# Transceiver_Module_Dev_Board_without_MCU.net
KiCad netlist of a schematic drawn in EAGLE
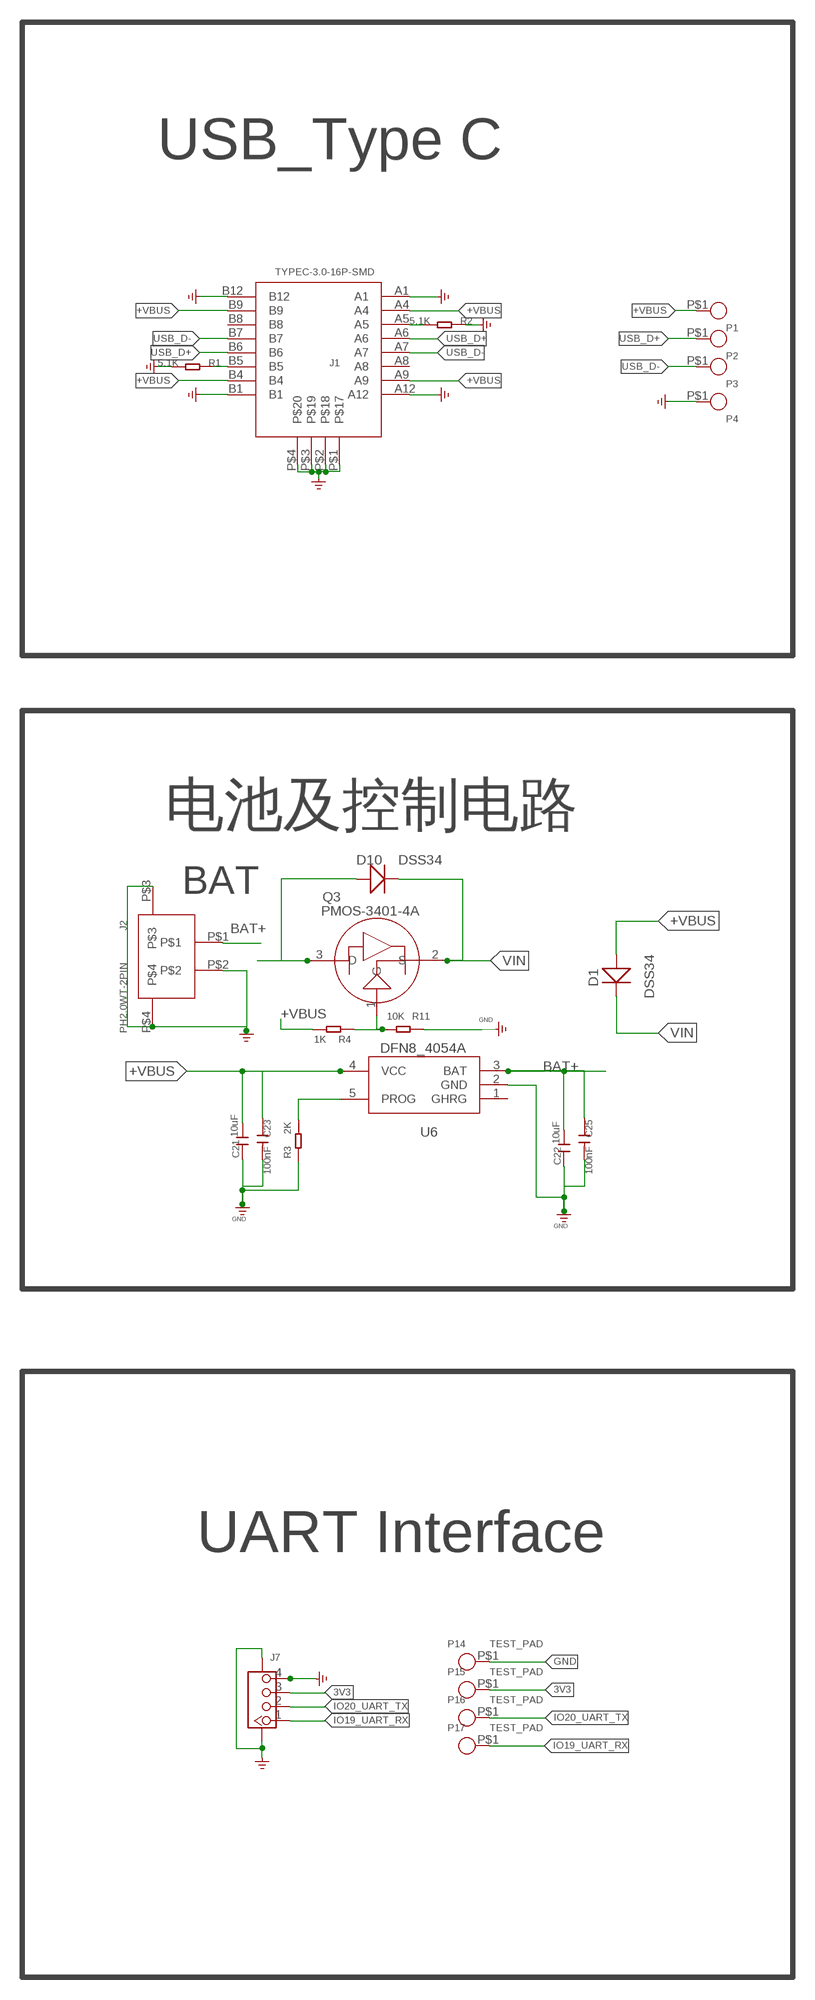
[diagram p0: schematic, sheet 1, part 1 of 2]
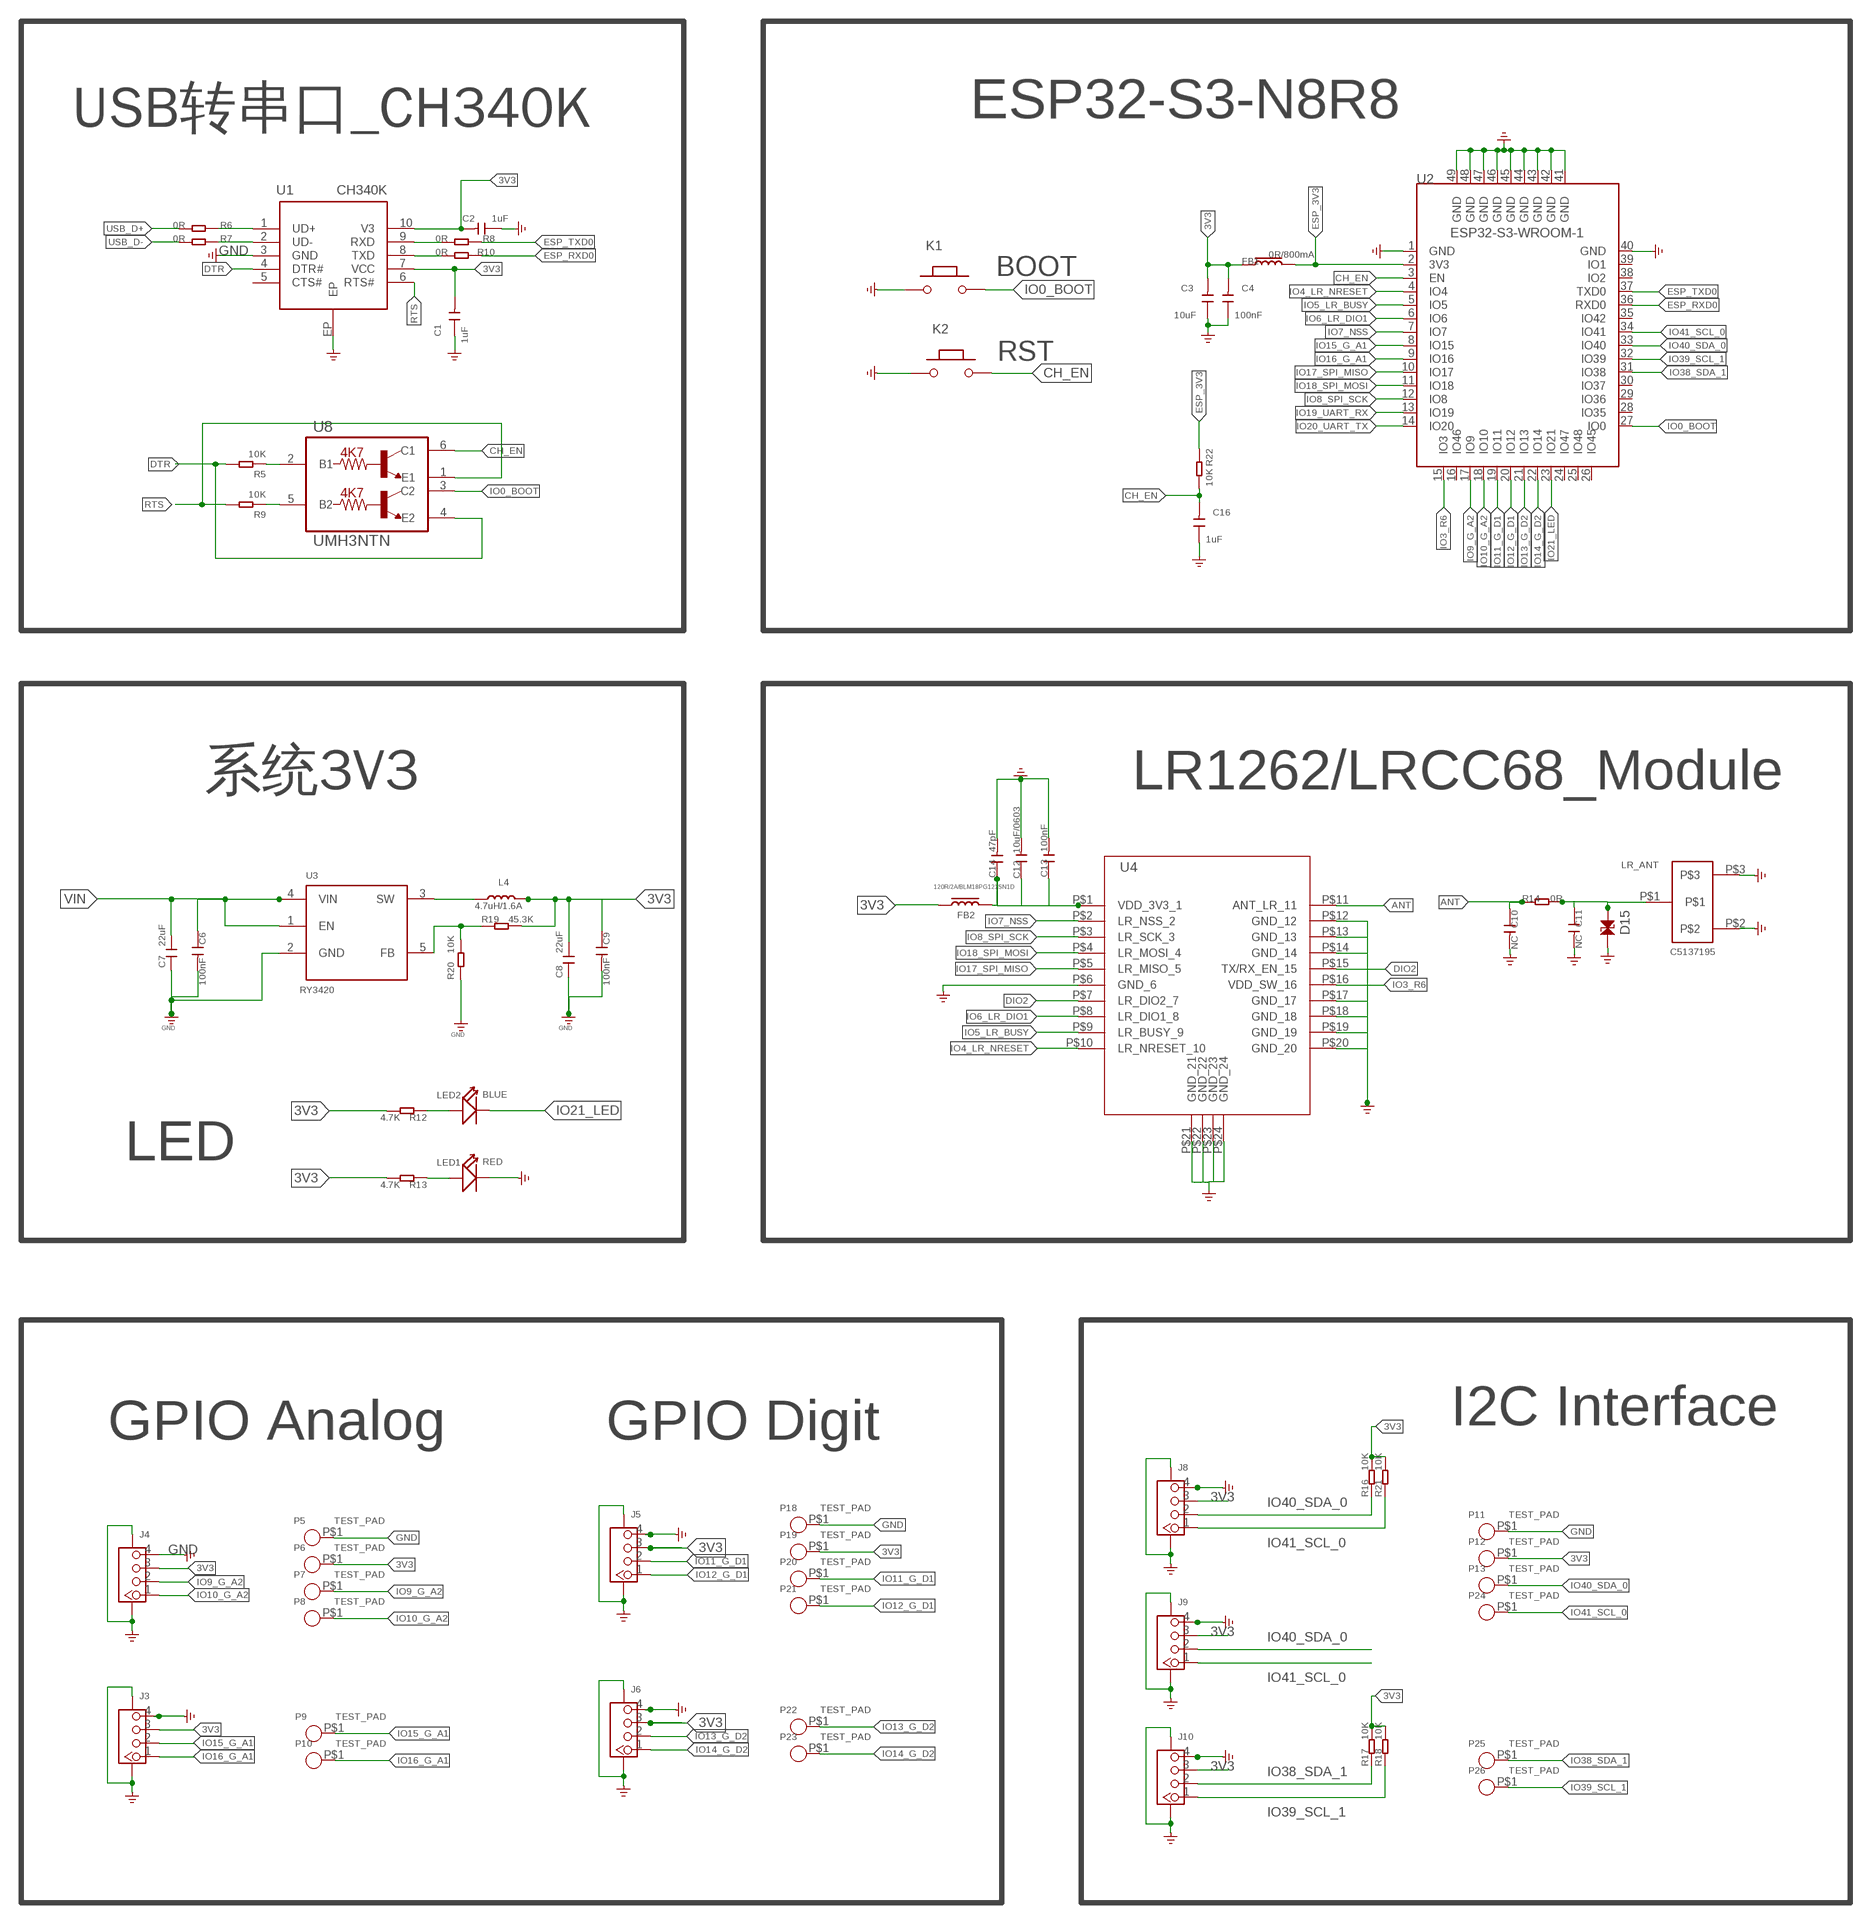
[diagram p1: schematic, sheet 1, part 2 of 2]

(export (version "E")
  (design (tool "Eeschema 10.0.6"))
  (components
    (comp (ref "C1")
      (value "1uF")
      (footprint "eagle-import:C0603")
      (libsource (lib "eagle-import") (part "CAP"))
    )
    (comp (ref "C2")
      (value "1uF")
      (footprint "eagle-import:C0603")
      (libsource (lib "eagle-import") (part "CAP"))
    )
    (comp (ref "C3")
      (value "10uF")
      (footprint "eagle-import:C0603")
      (libsource (lib "eagle-import") (part "CAP"))
    )
    (comp (ref "C4")
      (value "100nF")
      (footprint "eagle-import:C0603")
      (libsource (lib "eagle-import") (part "CAP"))
    )
    (comp (ref "C6")
      (value "100nF")
      (footprint "eagle-import:C0402")
      (libsource (lib "eagle-import") (part "SX1302_Module_CAPC0402-1"))
    )
    (comp (ref "C7")
      (value "22uF")
      (footprint "eagle-import:0603")
      (libsource (lib "eagle-import") (part "WGH_C0603"))
    )
    (comp (ref "C8")
      (value "22uF")
      (footprint "eagle-import:0603")
      (libsource (lib "eagle-import") (part "WGH_C0603"))
    )
    (comp (ref "C9")
      (value "100nF")
      (footprint "eagle-import:C0402")
      (libsource (lib "eagle-import") (part "SX1302_Module_CAPC0402-1"))
    )
    (comp (ref "C10")
      (value "NC")
      (footprint "eagle-import:C0402")
      (libsource (lib "eagle-import") (part "SX1302_Module_CAPC0402-1"))
    )
    (comp (ref "C11")
      (value "NC")
      (footprint "eagle-import:C0402")
      (libsource (lib "eagle-import") (part "SX1302_Module_CAPC0402-1"))
    )
    (comp (ref "C12")
      (value "10uF/0603")
      (footprint "eagle-import:C0603")
      (libsource (lib "eagle-import") (part "C0603"))
    )
    (comp (ref "C13")
      (value "100nF")
      (footprint "eagle-import:C0402")
      (libsource (lib "eagle-import") (part "SX1302_Module_CAPC0402-1"))
    )
    (comp (ref "C14")
      (value "47pF")
      (footprint "eagle-import:C0402")
      (libsource (lib "eagle-import") (part "SX1302_Module_CAPC0402-1"))
    )
    (comp (ref "C16")
      (value "1uF")
      (footprint "eagle-import:C0603")
      (libsource (lib "eagle-import") (part "CAP"))
    )
    (comp (ref "C21")
      (value "10uF")
      (footprint "eagle-import:0402")
      (libsource (lib "eagle-import") (part "C0402_W"))
    )
    (comp (ref "C22")
      (value "10uF")
      (footprint "eagle-import:0402")
      (libsource (lib "eagle-import") (part "C0402_W"))
    )
    (comp (ref "C23")
      (value "100nF")
      (footprint "eagle-import:C0402")
      (libsource (lib "eagle-import") (part "SX1302_Module_CAPC0402-1"))
    )
    (comp (ref "C25")
      (value "100nF")
      (footprint "eagle-import:C0402")
      (libsource (lib "eagle-import") (part "SX1302_Module_CAPC0402-1"))
    )
    (comp (ref "D1")
      (value "DSS34")
      (footprint "eagle-import:D_SOD123FL")
      (libsource (lib "eagle-import") (part "DIODE"))
    )
    (comp (ref "D10")
      (value "DSS34")
      (footprint "eagle-import:D_SOD123FL")
      (libsource (lib "eagle-import") (part "DIODE"))
    )
    (comp (ref "D15")
      (value "LXES15AAA1-153")
      (footprint "eagle-import:0402-ESD")
      (libsource (lib "eagle-import") (part "LXES15AAA1-153"))
    )
    (comp (ref "FB1")
      (value "0R/800mA")
      (footprint "eagle-import:L0603")
      (libsource (lib "eagle-import") (part "FBL0603"))
    )
    (comp (ref "FB2")
      (value "120R/2A/BLM18PG121SN1D")
      (footprint "eagle-import:L0603")
      (libsource (lib "eagle-import") (part "LoraWAN_Gateway_Mainboard_FBL0603"))
    )
    (comp (ref "J1")
      (value "TYPEC-3.0-16P-SMD")
      (footprint "eagle-import:USB-3.0TYPEC-SMD")
      (libsource (lib "eagle-import") (part "TYPEC-3.0-16P-SMD"))
    )
    (comp (ref "J2")
      (value "PH2.0WT-2PIN")
      (footprint "eagle-import:PH2.0WT-2PIN")
      (libsource (lib "eagle-import") (part "PH2.0WT-2PIN"))
    )
    (comp (ref "J3")
      (value "CONNECTOR_TWIG-4P-2.0-SMD-FEMALE-REINFORCE90D")
      (footprint "eagle-import:CONNECTOR_4P-SMD-2.0-90D")
      (libsource (lib "eagle-import") (part "CONNECTOR_TWIG-4P-2.0-SMD-FEMALE-REINFORCE90D"))
    )
    (comp (ref "J4")
      (value "CONNECTOR_TWIG-4P-2.0-SMD-FEMALE-REINFORCE90D")
      (footprint "eagle-import:CONNECTOR_4P-SMD-2.0-90D")
      (libsource (lib "eagle-import") (part "CONNECTOR_TWIG-4P-2.0-SMD-FEMALE-REINFORCE90D"))
    )
    (comp (ref "J5")
      (value "CONNECTOR_TWIG-4P-2.0-SMD-FEMALE-REINFORCE90D")
      (footprint "eagle-import:CONNECTOR_4P-SMD-2.0-90D")
      (libsource (lib "eagle-import") (part "CONNECTOR_TWIG-4P-2.0-SMD-FEMALE-REINFORCE90D"))
    )
    (comp (ref "J6")
      (value "CONNECTOR_TWIG-4P-2.0-SMD-FEMALE-REINFORCE90D")
      (footprint "eagle-import:CONNECTOR_4P-SMD-2.0-90D")
      (libsource (lib "eagle-import") (part "CONNECTOR_TWIG-4P-2.0-SMD-FEMALE-REINFORCE90D"))
    )
    (comp (ref "J7")
      (value "CONNECTOR_TWIG-4P-2.0-SMD-FEMALE-REINFORCE90D")
      (footprint "eagle-import:CONNECTOR_4P-SMD-2.0-90D")
      (libsource (lib "eagle-import") (part "CONNECTOR_TWIG-4P-2.0-SMD-FEMALE-REINFORCE90D"))
    )
    (comp (ref "J8")
      (value "CONNECTOR_TWIG-4P-2.0-SMD-FEMALE-REINFORCE90D")
      (footprint "eagle-import:CONNECTOR_4P-SMD-2.0-90D")
      (libsource (lib "eagle-import") (part "CONNECTOR_TWIG-4P-2.0-SMD-FEMALE-REINFORCE90D"))
    )
    (comp (ref "J9")
      (value "CONNECTOR_TWIG-4P-2.0-SMD-FEMALE-REINFORCE90D")
      (footprint "eagle-import:CONNECTOR_4P-SMD-2.0-90D")
      (libsource (lib "eagle-import") (part "CONNECTOR_TWIG-4P-2.0-SMD-FEMALE-REINFORCE90D"))
    )
    (comp (ref "J10")
      (value "CONNECTOR_TWIG-4P-2.0-SMD-FEMALE-REINFORCE90D")
      (footprint "eagle-import:CONNECTOR_4P-SMD-2.0-90D")
      (libsource (lib "eagle-import") (part "CONNECTOR_TWIG-4P-2.0-SMD-FEMALE-REINFORCE90D"))
    )
    (comp (ref "K1")
      (value "BUTTON")
      (footprint "eagle-import:157SW")
      (libsource (lib "eagle-import") (part "PB157"))
    )
    (comp (ref "K2")
      (value "BUTTON")
      (footprint "eagle-import:157SW")
      (libsource (lib "eagle-import") (part "PB157"))
    )
    (comp (ref "L4")
      (value "4.7uH/1.6A")
      (footprint "eagle-import:A9G_DISCRETE_L0805")
      (libsource (lib "eagle-import") (part "A9G_DISCRETE_L0805"))
    )
    (comp (ref "LED1")
      (value "RED")
      (footprint "eagle-import:DISCRETE_LED-0603")
      (libsource (lib "eagle-import") (part "DISCRETE_LED0603"))
    )
    (comp (ref "LED2")
      (value "BLUE")
      (footprint "eagle-import:DISCRETE_LED-0603")
      (libsource (lib "eagle-import") (part "DISCRETE_LED0603"))
    )
    (comp (ref "LR_ANT")
      (value "C5137195")
      (footprint "eagle-import:MYSELF_IPEX1")
      (libsource (lib "eagle-import") (part "MYSELF_IPEX"))
    )
    (comp (ref "P1")
      (value "TEST_PADPAD-1.5MM")
      (footprint "eagle-import:TEST_PAD-1.5MM")
      (libsource (lib "eagle-import") (part "CrowPanel_Advance_HMI_TEST_PADPAD-1.5MM"))
    )
    (comp (ref "P2")
      (value "TEST_PADPAD-1.5MM")
      (footprint "eagle-import:TEST_PAD-1.5MM")
      (libsource (lib "eagle-import") (part "CrowPanel_Advance_HMI_TEST_PADPAD-1.5MM"))
    )
    (comp (ref "P3")
      (value "TEST_PADPAD-1.5MM")
      (footprint "eagle-import:TEST_PAD-1.5MM")
      (libsource (lib "eagle-import") (part "CrowPanel_Advance_HMI_TEST_PADPAD-1.5MM"))
    )
    (comp (ref "P4")
      (value "TEST_PADPAD-1.5MM")
      (footprint "eagle-import:TEST_PAD-1.5MM")
      (libsource (lib "eagle-import") (part "CrowPanel_Advance_HMI_TEST_PADPAD-1.5MM"))
    )
    (comp (ref "P5")
      (value "TEST_PAD")
      (footprint "eagle-import:TEST_PAD-1.5MM")
      (libsource (lib "eagle-import") (part "TEST_PADPAD-1.5MM"))
    )
    (comp (ref "P6")
      (value "TEST_PAD")
      (footprint "eagle-import:TEST_PAD-1.5MM")
      (libsource (lib "eagle-import") (part "TEST_PADPAD-1.5MM"))
    )
    (comp (ref "P7")
      (value "TEST_PAD")
      (footprint "eagle-import:TEST_PAD-1.5MM")
      (libsource (lib "eagle-import") (part "TEST_PADPAD-1.5MM"))
    )
    (comp (ref "P8")
      (value "TEST_PAD")
      (footprint "eagle-import:TEST_PAD-1.5MM")
      (libsource (lib "eagle-import") (part "TEST_PADPAD-1.5MM"))
    )
    (comp (ref "P9")
      (value "TEST_PAD")
      (footprint "eagle-import:TEST_PAD-1.5MM")
      (libsource (lib "eagle-import") (part "TEST_PADPAD-1.5MM"))
    )
    (comp (ref "P10")
      (value "TEST_PAD")
      (footprint "eagle-import:TEST_PAD-1.5MM")
      (libsource (lib "eagle-import") (part "TEST_PADPAD-1.5MM"))
    )
    (comp (ref "P11")
      (value "TEST_PAD")
      (footprint "eagle-import:TEST_PAD-1.5MM")
      (libsource (lib "eagle-import") (part "TEST_PADPAD-1.5MM"))
    )
    (comp (ref "P12")
      (value "TEST_PAD")
      (footprint "eagle-import:TEST_PAD-1.5MM")
      (libsource (lib "eagle-import") (part "TEST_PADPAD-1.5MM"))
    )
    (comp (ref "P13")
      (value "TEST_PAD")
      (footprint "eagle-import:TEST_PAD-1.5MM")
      (libsource (lib "eagle-import") (part "TEST_PADPAD-1.5MM"))
    )
    (comp (ref "P14")
      (value "TEST_PAD")
      (footprint "eagle-import:TEST_PAD-1.5MM")
      (libsource (lib "eagle-import") (part "TEST_PADPAD-1.5MM"))
    )
    (comp (ref "P15")
      (value "TEST_PAD")
      (footprint "eagle-import:TEST_PAD-1.5MM")
      (libsource (lib "eagle-import") (part "TEST_PADPAD-1.5MM"))
    )
    (comp (ref "P16")
      (value "TEST_PAD")
      (footprint "eagle-import:TEST_PAD-1.5MM")
      (libsource (lib "eagle-import") (part "TEST_PADPAD-1.5MM"))
    )
    (comp (ref "P17")
      (value "TEST_PAD")
      (footprint "eagle-import:TEST_PAD-1.5MM")
      (libsource (lib "eagle-import") (part "TEST_PADPAD-1.5MM"))
    )
    (comp (ref "P18")
      (value "TEST_PAD")
      (footprint "eagle-import:TEST_PAD-1.5MM")
      (libsource (lib "eagle-import") (part "TEST_PADPAD-1.5MM"))
    )
    (comp (ref "P19")
      (value "TEST_PAD")
      (footprint "eagle-import:TEST_PAD-1.5MM")
      (libsource (lib "eagle-import") (part "TEST_PADPAD-1.5MM"))
    )
    (comp (ref "P20")
      (value "TEST_PAD")
      (footprint "eagle-import:TEST_PAD-1.5MM")
      (libsource (lib "eagle-import") (part "TEST_PADPAD-1.5MM"))
    )
    (comp (ref "P21")
      (value "TEST_PAD")
      (footprint "eagle-import:TEST_PAD-1.5MM")
      (libsource (lib "eagle-import") (part "TEST_PADPAD-1.5MM"))
    )
    (comp (ref "P22")
      (value "TEST_PAD")
      (footprint "eagle-import:TEST_PAD-1.5MM")
      (libsource (lib "eagle-import") (part "TEST_PADPAD-1.5MM"))
    )
    (comp (ref "P23")
      (value "TEST_PAD")
      (footprint "eagle-import:TEST_PAD-1.5MM")
      (libsource (lib "eagle-import") (part "TEST_PADPAD-1.5MM"))
    )
    (comp (ref "P24")
      (value "TEST_PAD")
      (footprint "eagle-import:TEST_PAD-1.5MM")
      (libsource (lib "eagle-import") (part "TEST_PADPAD-1.5MM"))
    )
    (comp (ref "P25")
      (value "TEST_PAD")
      (footprint "eagle-import:TEST_PAD-1.5MM")
      (libsource (lib "eagle-import") (part "TEST_PADPAD-1.5MM"))
    )
    (comp (ref "P26")
      (value "TEST_PAD")
      (footprint "eagle-import:TEST_PAD-1.5MM")
      (libsource (lib "eagle-import") (part "TEST_PADPAD-1.5MM"))
    )
    (comp (ref "Q3")
      (value "PMOS-3401-4A")
      (footprint "eagle-import:SOT-23")
      (libsource (lib "eagle-import") (part "P-MOS-SOT23"))
    )
    (comp (ref "R1")
      (value "5.1K")
      (footprint "eagle-import:R0603-SP")
      (libsource (lib "eagle-import") (part "RES-0603"))
    )
    (comp (ref "R2")
      (value "5.1K")
      (footprint "eagle-import:R0603-SP")
      (libsource (lib "eagle-import") (part "RES-0603"))
    )
    (comp (ref "R3")
      (value "2K")
      (footprint "eagle-import:0402")
      (libsource (lib "eagle-import") (part "R0402-1"))
    )
    (comp (ref "R4")
      (value "1K")
      (footprint "eagle-import:0402")
      (libsource (lib "eagle-import") (part "R0402-1"))
    )
    (comp (ref "R5")
      (value "10K")
      (footprint "eagle-import:R0603-SP")
      (libsource (lib "eagle-import") (part "RES-0603"))
    )
    (comp (ref "R6")
      (value "0R")
      (footprint "eagle-import:R0603-SP")
      (libsource (lib "eagle-import") (part "RES-0603"))
    )
    (comp (ref "R7")
      (value "0R")
      (footprint "eagle-import:R0603-SP")
      (libsource (lib "eagle-import") (part "RES-0603"))
    )
    (comp (ref "R8")
      (value "0R")
      (footprint "eagle-import:R0603-SP")
      (libsource (lib "eagle-import") (part "RES-0603"))
    )
    (comp (ref "R9")
      (value "10K")
      (footprint "eagle-import:R0603-SP")
      (libsource (lib "eagle-import") (part "RES-0603"))
    )
    (comp (ref "R10")
      (value "0R")
      (footprint "eagle-import:R0603-SP")
      (libsource (lib "eagle-import") (part "RES-0603"))
    )
    (comp (ref "R11")
      (value "10K")
      (footprint "eagle-import:0402")
      (libsource (lib "eagle-import") (part "R0402-1"))
    )
    (comp (ref "R12")
      (value "4.7K")
      (footprint "eagle-import:0402")
      (libsource (lib "eagle-import") (part "R0402-1"))
    )
    (comp (ref "R13")
      (value "4.7K")
      (footprint "eagle-import:0402")
      (libsource (lib "eagle-import") (part "R0402-1"))
    )
    (comp (ref "R14")
      (value "0R")
      (footprint "eagle-import:R0402")
      (libsource (lib "eagle-import") (part "LoraWAN_Gateway_Mainboard_RES-0402"))
    )
    (comp (ref "R16")
      (value "10K")
      (footprint "eagle-import:0402")
      (libsource (lib "eagle-import") (part "R0402-1"))
    )
    (comp (ref "R17")
      (value "10K")
      (footprint "eagle-import:0402")
      (libsource (lib "eagle-import") (part "R0402-1"))
    )
    (comp (ref "R18")
      (value "10K")
      (footprint "eagle-import:0402")
      (libsource (lib "eagle-import") (part "R0402-1"))
    )
    (comp (ref "R19")
      (value "45.3K")
      (footprint "eagle-import:0402")
      (libsource (lib "eagle-import") (part "R0402-1"))
    )
    (comp (ref "R20")
      (value "10K")
      (footprint "eagle-import:0402")
      (libsource (lib "eagle-import") (part "R0402-1"))
    )
    (comp (ref "R21")
      (value "10K")
      (footprint "eagle-import:0402")
      (libsource (lib "eagle-import") (part "R0402-1"))
    )
    (comp (ref "R22")
      (value "10K")
      (footprint "eagle-import:R0603-SP")
      (libsource (lib "eagle-import") (part "RES-0603"))
    )
    (comp (ref "U1")
      (value "CH340K")
      (footprint "eagle-import:ESOP-10-EP-150MIL")
      (libsource (lib "eagle-import") (part "CH340K"))
    )
    (comp (ref "U2")
      (value "ESP32-S3-WROOM-1")
      (footprint "eagle-import:ESP32-S3-WROOM-1-SMD41")
      (libsource (lib "eagle-import") (part "ESP32-S3-WROOM-1"))
    )
    (comp (ref "U3")
      (value "RY3420")
      (footprint "eagle-import:CROWBOT_-V1.0-20220525_A_XBJ_SOT23-5")
      (libsource (lib "eagle-import") (part "CROWBOT_-V1.0-20220525_A_XBJ_HM3420B"))
    )
    (comp (ref "U4")
      (value "LR1262_LRCC68_MD_1010MM")
      (footprint "eagle-import:LR1262_LRCC68_MD_10_10MM")
      (libsource (lib "eagle-import") (part "LR1262_LRCC68_MD_1010MM"))
    )
    (comp (ref "U6")
      (value "DFN8_4054A")
      (footprint "eagle-import:DFN8_SOP23-5")
      (libsource (lib "eagle-import") (part "DFN8_4054A"))
    )
    (comp (ref "U8")
      (value "UMH3NTN")
      (footprint "eagle-import:SOP65P210X100-6N")
      (fields (field (name "MF") "Rohm"))
      (libsource (lib "eagle-import") (part "UMH3NTN"))
    )
  )
  (nets
    (net (code "1") (name "+VBUS") (class "Default")
      (node (ref "C21") (pin "2") (pinfunction "2_2") (pintype "passive"))
      (node (ref "C23") (pin "1") (pinfunction "1_1") (pintype "passive"))
      (node (ref "D1") (pin "+") (pinfunction "+_+") (pintype "passive"))
      (node (ref "J1") (pin "A4") (pinfunction "A4_A4") (pintype "bidirectional"))
      (node (ref "J1") (pin "A9") (pinfunction "A9_A9") (pintype "bidirectional"))
      (node (ref "J1") (pin "B4") (pinfunction "B4_B4") (pintype "bidirectional"))
      (node (ref "J1") (pin "B9") (pinfunction "B9_B9") (pintype "bidirectional"))
      (node (ref "P1") (pin "P$1") (pinfunction "P$1_P$1") (pintype "bidirectional"))
      (node (ref "R4") (pin "2") (pinfunction "2_2") (pintype "passive"))
      (node (ref "U6") (pin "4") (pinfunction "VCC_4") (pintype "bidirectional"))
    )
    (net (code "2") (name "/BAT+") (class "Default")
      (node (ref "C22") (pin "2") (pinfunction "2_2") (pintype "passive"))
      (node (ref "C25") (pin "1") (pinfunction "1_1") (pintype "passive"))
      (node (ref "D10") (pin "+") (pinfunction "+_+") (pintype "passive"))
      (node (ref "J2") (pin "P$1") (pinfunction "P$1_P$1") (pintype "bidirectional"))
      (node (ref "Q3") (pin "3") (pinfunction "D_3") (pintype "bidirectional"))
      (node (ref "U6") (pin "3") (pinfunction "BAT_3") (pintype "bidirectional"))
    )
    (net (code "3") (name "3V3") (class "Default")
      (node (ref "C1") (pin "2") (pinfunction "2_2") (pintype "passive"))
      (node (ref "C2") (pin "2") (pinfunction "2_2") (pintype "passive"))
      (node (ref "C3") (pin "2") (pinfunction "2_2") (pintype "passive"))
      (node (ref "C4") (pin "2") (pinfunction "2_2") (pintype "passive"))
      (node (ref "C8") (pin "2") (pinfunction "2_2") (pintype "passive"))
      (node (ref "C9") (pin "1") (pinfunction "1_1") (pintype "passive"))
      (node (ref "FB1") (pin "1") (pinfunction "1_1") (pintype "passive"))
      (node (ref "FB2") (pin "1") (pinfunction "1_1") (pintype "passive"))
      (node (ref "J10") (pin "3") (pinfunction "3_3") (pintype "bidirectional"))
      (node (ref "J3") (pin "3") (pinfunction "3_3") (pintype "bidirectional"))
      (node (ref "J4") (pin "3") (pinfunction "3_3") (pintype "bidirectional"))
      (node (ref "J5") (pin "3") (pinfunction "3_3") (pintype "bidirectional"))
      (node (ref "J6") (pin "3") (pinfunction "3_3") (pintype "bidirectional"))
      (node (ref "J7") (pin "3") (pinfunction "3_3") (pintype "bidirectional"))
      (node (ref "J8") (pin "3") (pinfunction "3_3") (pintype "bidirectional"))
      (node (ref "J9") (pin "3") (pinfunction "3_3") (pintype "bidirectional"))
      (node (ref "L4") (pin "2") (pinfunction "2_2") (pintype "passive"))
      (node (ref "P12") (pin "P$1") (pinfunction "P$1_P$1") (pintype "bidirectional"))
      (node (ref "P15") (pin "P$1") (pinfunction "P$1_P$1") (pintype "bidirectional"))
      (node (ref "P19") (pin "P$1") (pinfunction "P$1_P$1") (pintype "bidirectional"))
      (node (ref "P6") (pin "P$1") (pinfunction "P$1_P$1") (pintype "bidirectional"))
      (node (ref "R12") (pin "2") (pinfunction "2_2") (pintype "passive"))
      (node (ref "R13") (pin "2") (pinfunction "2_2") (pintype "passive"))
      (node (ref "R16") (pin "2") (pinfunction "2_2") (pintype "passive"))
      (node (ref "R17") (pin "2") (pinfunction "2_2") (pintype "passive"))
      (node (ref "R18") (pin "2") (pinfunction "2_2") (pintype "passive"))
      (node (ref "R19") (pin "2") (pinfunction "2_2") (pintype "passive"))
      (node (ref "R21") (pin "2") (pinfunction "2_2") (pintype "passive"))
      (node (ref "U1") (pin "10") (pinfunction "V3_10") (pintype "bidirectional"))
      (node (ref "U1") (pin "7") (pinfunction "VCC_7") (pintype "bidirectional"))
    )
    (net (code "4") (name "ANT") (class "Default")
      (node (ref "C10") (pin "1") (pinfunction "1_1") (pintype "passive"))
      (node (ref "R14") (pin "1") (pinfunction "1_1") (pintype "passive"))
      (node (ref "U4") (pin "P$11") (pinfunction "ANT_LR_11_P$11") (pintype "bidirectional"))
    )
    (net (code "5") (name "CH_EN") (class "Default")
      (node (ref "C16") (pin "2") (pinfunction "2_2") (pintype "passive"))
      (node (ref "K2") (pin "2") (pinfunction "2_2") (pintype "passive"))
      (node (ref "R22") (pin "2") (pinfunction "2_2") (pintype "passive"))
      (node (ref "U2") (pin "3") (pinfunction "EN_3") (pintype "bidirectional"))
      (node (ref "U8") (pin "6") (pinfunction "C1_6") (pintype "bidirectional"))
    )
    (net (code "6") (name "DIO2") (class "Default")
      (node (ref "U4") (pin "P$15") (pinfunction "TX/RX_EN_15_P$15") (pintype "bidirectional"))
      (node (ref "U4") (pin "P$7") (pinfunction "LR_DIO2_7_P$7") (pintype "bidirectional"))
    )
    (net (code "7") (name "DTR") (class "Default")
      (node (ref "R5") (pin "2") (pinfunction "2_2") (pintype "passive"))
      (node (ref "U1") (pin "4") (pinfunction "DTR#_4") (pintype "bidirectional"))
      (node (ref "U8") (pin "4") (pinfunction "E2_4") (pintype "bidirectional"))
    )
    (net (code "8") (name "ESP_3V3") (class "Default")
      (node (ref "FB1") (pin "2") (pinfunction "2_2") (pintype "passive"))
      (node (ref "R22") (pin "1") (pinfunction "1_1") (pintype "passive"))
      (node (ref "U2") (pin "2") (pinfunction "3V3_2") (pintype "bidirectional"))
    )
    (net (code "9") (name "ESP_RXD0") (class "Default")
      (node (ref "R10") (pin "1") (pinfunction "1_1") (pintype "passive"))
      (node (ref "U2") (pin "36") (pinfunction "RXD0_36") (pintype "bidirectional"))
    )
    (net (code "10") (name "ESP_TXD0") (class "Default")
      (node (ref "R8") (pin "1") (pinfunction "1_1") (pintype "passive"))
      (node (ref "U2") (pin "37") (pinfunction "TXD0_37") (pintype "bidirectional"))
    )
    (net (code "11") (name "GND") (class "Default")
      (node (ref "C1") (pin "1") (pinfunction "1_1") (pintype "passive"))
      (node (ref "C10") (pin "2") (pinfunction "2_2") (pintype "passive"))
      (node (ref "C11") (pin "2") (pinfunction "2_2") (pintype "passive"))
      (node (ref "C12") (pin "2") (pinfunction "2_2") (pintype "passive"))
      (node (ref "C13") (pin "2") (pinfunction "2_2") (pintype "passive"))
      (node (ref "C14") (pin "2") (pinfunction "2_2") (pintype "passive"))
      (node (ref "C16") (pin "1") (pinfunction "1_1") (pintype "passive"))
      (node (ref "C2") (pin "1") (pinfunction "1_1") (pintype "passive"))
      (node (ref "C21") (pin "1") (pinfunction "1_1") (pintype "passive"))
      (node (ref "C22") (pin "1") (pinfunction "1_1") (pintype "passive"))
      (node (ref "C23") (pin "2") (pinfunction "2_2") (pintype "passive"))
      (node (ref "C25") (pin "2") (pinfunction "2_2") (pintype "passive"))
      (node (ref "C3") (pin "1") (pinfunction "1_1") (pintype "passive"))
      (node (ref "C4") (pin "1") (pinfunction "1_1") (pintype "passive"))
      (node (ref "C6") (pin "2") (pinfunction "2_2") (pintype "passive"))
      (node (ref "C7") (pin "1") (pinfunction "1_1") (pintype "passive"))
      (node (ref "C8") (pin "1") (pinfunction "1_1") (pintype "passive"))
      (node (ref "C9") (pin "2") (pinfunction "2_2") (pintype "passive"))
      (node (ref "D15") (pin "1") (pinfunction "1_1") (pintype "bidirectional"))
      (node (ref "J1") (pin "A1") (pinfunction "A1_A1") (pintype "bidirectional"))
      (node (ref "J1") (pin "A12") (pinfunction "A12_A12") (pintype "bidirectional"))
      (node (ref "J1") (pin "B1") (pinfunction "B1_B1") (pintype "bidirectional"))
      (node (ref "J1") (pin "B12") (pinfunction "B12_B12") (pintype "bidirectional"))
      (node (ref "J1") (pin "P$1") (pinfunction "P$17_P$1") (pintype "bidirectional"))
      (node (ref "J1") (pin "P$2") (pinfunction "P$18_P$2") (pintype "bidirectional"))
      (node (ref "J1") (pin "P$3") (pinfunction "P$19_P$3") (pintype "bidirectional"))
      (node (ref "J1") (pin "P$4") (pinfunction "P$20_P$4") (pintype "bidirectional"))
      (node (ref "J10") (pin "4") (pinfunction "4_4") (pintype "bidirectional"))
      (node (ref "J10") (pin "SS1") (pinfunction "SS1_SS1") (pintype "bidirectional"))
      (node (ref "J10") (pin "SS2") (pinfunction "SS2_SS2") (pintype "bidirectional"))
      (node (ref "J2") (pin "P$2") (pinfunction "P$2_P$2") (pintype "bidirectional"))
      (node (ref "J2") (pin "P$3") (pinfunction "P$3_P$3") (pintype "bidirectional"))
      (node (ref "J2") (pin "P$4") (pinfunction "P$4_P$4") (pintype "bidirectional"))
      (node (ref "J3") (pin "4") (pinfunction "4_4") (pintype "bidirectional"))
      (node (ref "J3") (pin "SS1") (pinfunction "SS1_SS1") (pintype "bidirectional"))
      (node (ref "J3") (pin "SS2") (pinfunction "SS2_SS2") (pintype "bidirectional"))
      (node (ref "J4") (pin "4") (pinfunction "4_4") (pintype "bidirectional"))
      (node (ref "J4") (pin "SS1") (pinfunction "SS1_SS1") (pintype "bidirectional"))
      (node (ref "J4") (pin "SS2") (pinfunction "SS2_SS2") (pintype "bidirectional"))
      (node (ref "J5") (pin "4") (pinfunction "4_4") (pintype "bidirectional"))
      (node (ref "J5") (pin "SS1") (pinfunction "SS1_SS1") (pintype "bidirectional"))
      (node (ref "J5") (pin "SS2") (pinfunction "SS2_SS2") (pintype "bidirectional"))
      (node (ref "J6") (pin "4") (pinfunction "4_4") (pintype "bidirectional"))
      (node (ref "J6") (pin "SS1") (pinfunction "SS1_SS1") (pintype "bidirectional"))
      (node (ref "J6") (pin "SS2") (pinfunction "SS2_SS2") (pintype "bidirectional"))
      (node (ref "J7") (pin "4") (pinfunction "4_4") (pintype "bidirectional"))
      (node (ref "J7") (pin "SS1") (pinfunction "SS1_SS1") (pintype "bidirectional"))
      (node (ref "J7") (pin "SS2") (pinfunction "SS2_SS2") (pintype "bidirectional"))
      (node (ref "J8") (pin "4") (pinfunction "4_4") (pintype "bidirectional"))
      (node (ref "J8") (pin "SS1") (pinfunction "SS1_SS1") (pintype "bidirectional"))
      (node (ref "J8") (pin "SS2") (pinfunction "SS2_SS2") (pintype "bidirectional"))
      (node (ref "J9") (pin "4") (pinfunction "4_4") (pintype "bidirectional"))
      (node (ref "J9") (pin "SS1") (pinfunction "SS1_SS1") (pintype "bidirectional"))
      (node (ref "J9") (pin "SS2") (pinfunction "SS2_SS2") (pintype "bidirectional"))
      (node (ref "K1") (pin "1") (pinfunction "1_1") (pintype "passive"))
      (node (ref "K2") (pin "1") (pinfunction "1_1") (pintype "passive"))
      (node (ref "LED1") (pin "-") (pinfunction "-_-") (pintype "passive"))
      (node (ref "LR_ANT") (pin "P$2") (pinfunction "P$2_P$2") (pintype "bidirectional"))
      (node (ref "LR_ANT") (pin "P$3") (pinfunction "P$3_P$3") (pintype "bidirectional"))
      (node (ref "P11") (pin "P$1") (pinfunction "P$1_P$1") (pintype "bidirectional"))
      (node (ref "P14") (pin "P$1") (pinfunction "P$1_P$1") (pintype "bidirectional"))
      (node (ref "P18") (pin "P$1") (pinfunction "P$1_P$1") (pintype "bidirectional"))
      (node (ref "P4") (pin "P$1") (pinfunction "P$1_P$1") (pintype "bidirectional"))
      (node (ref "P5") (pin "P$1") (pinfunction "P$1_P$1") (pintype "bidirectional"))
      (node (ref "R1") (pin "2") (pinfunction "2_2") (pintype "passive"))
      (node (ref "R11") (pin "1") (pinfunction "1_1") (pintype "passive"))
      (node (ref "R2") (pin "1") (pinfunction "1_1") (pintype "passive"))
      (node (ref "R20") (pin "1") (pinfunction "1_1") (pintype "passive"))
      (node (ref "R3") (pin "1") (pinfunction "1_1") (pintype "passive"))
      (node (ref "U1") (pin "3") (pinfunction "GND_3") (pintype "bidirectional"))
      (node (ref "U1") (pin "EP") (pinfunction "EP_EP") (pintype "bidirectional"))
      (node (ref "U2") (pin "1") (pinfunction "GND_1") (pintype "bidirectional"))
      (node (ref "U2") (pin "40") (pinfunction "GND_40") (pintype "bidirectional"))
      (node (ref "U2") (pin "41") (pinfunction "GND_41") (pintype "bidirectional"))
      (node (ref "U2") (pin "42") (pinfunction "GND_42") (pintype "bidirectional"))
      (node (ref "U2") (pin "43") (pinfunction "GND_43") (pintype "bidirectional"))
      (node (ref "U2") (pin "44") (pinfunction "GND_44") (pintype "bidirectional"))
      (node (ref "U2") (pin "45") (pinfunction "GND_45") (pintype "bidirectional"))
      (node (ref "U2") (pin "46") (pinfunction "GND_46") (pintype "bidirectional"))
      (node (ref "U2") (pin "47") (pinfunction "GND_47") (pintype "bidirectional"))
      (node (ref "U2") (pin "48") (pinfunction "GND_48") (pintype "bidirectional"))
      (node (ref "U2") (pin "49") (pinfunction "GND_49") (pintype "bidirectional"))
      (node (ref "U3") (pin "2") (pinfunction "GND_2") (pintype "bidirectional"))
      (node (ref "U4") (pin "P$12") (pinfunction "GND_12_P$12") (pintype "bidirectional"))
      (node (ref "U4") (pin "P$13") (pinfunction "GND_13_P$13") (pintype "bidirectional"))
      (node (ref "U4") (pin "P$14") (pinfunction "GND_14_P$14") (pintype "bidirectional"))
      (node (ref "U4") (pin "P$17") (pinfunction "GND_17_P$17") (pintype "bidirectional"))
      (node (ref "U4") (pin "P$18") (pinfunction "GND_18_P$18") (pintype "bidirectional"))
      (node (ref "U4") (pin "P$19") (pinfunction "GND_19_P$19") (pintype "bidirectional"))
      (node (ref "U4") (pin "P$20") (pinfunction "GND_20_P$20") (pintype "bidirectional"))
      (node (ref "U4") (pin "P$21") (pinfunction "GND_21_P$21") (pintype "bidirectional"))
      (node (ref "U4") (pin "P$22") (pinfunction "GND_22_P$22") (pintype "bidirectional"))
      (node (ref "U4") (pin "P$23") (pinfunction "GND_23_P$23") (pintype "bidirectional"))
      (node (ref "U4") (pin "P$24") (pinfunction "GND_24_P$24") (pintype "bidirectional"))
      (node (ref "U4") (pin "P$6") (pinfunction "GND_6_P$6") (pintype "bidirectional"))
      (node (ref "U6") (pin "2") (pinfunction "GND_2") (pintype "bidirectional"))
    )
    (net (code "12") (name "IO0_BOOT") (class "Default")
      (node (ref "K1") (pin "2") (pinfunction "2_2") (pintype "passive"))
      (node (ref "U2") (pin "27") (pinfunction "IO0_27") (pintype "bidirectional"))
      (node (ref "U8") (pin "3") (pinfunction "C2_3") (pintype "bidirectional"))
    )
    (net (code "13") (name "IO3_R6") (class "Default")
      (node (ref "U2") (pin "15") (pinfunction "IO3_15") (pintype "bidirectional"))
      (node (ref "U4") (pin "P$16") (pinfunction "VDD_SW_16_P$16") (pintype "bidirectional"))
    )
    (net (code "14") (name "IO4_LR_NRESET") (class "Default")
      (node (ref "U2") (pin "4") (pinfunction "IO4_4") (pintype "bidirectional"))
      (node (ref "U4") (pin "P$10") (pinfunction "LR_NRESET_10_P$10") (pintype "bidirectional"))
    )
    (net (code "15") (name "IO5_LR_BUSY") (class "Default")
      (node (ref "U2") (pin "5") (pinfunction "IO5_5") (pintype "bidirectional"))
      (node (ref "U4") (pin "P$9") (pinfunction "LR_BUSY_9_P$9") (pintype "bidirectional"))
    )
    (net (code "16") (name "IO6_LR_DIO1") (class "Default")
      (node (ref "U2") (pin "6") (pinfunction "IO6_6") (pintype "bidirectional"))
      (node (ref "U4") (pin "P$8") (pinfunction "LR_DIO1_8_P$8") (pintype "bidirectional"))
    )
    (net (code "17") (name "IO7_NSS") (class "Default")
      (node (ref "U2") (pin "7") (pinfunction "IO7_7") (pintype "bidirectional"))
      (node (ref "U4") (pin "P$2") (pinfunction "LR_NSS_2_P$2") (pintype "bidirectional"))
    )
    (net (code "18") (name "IO8_SPI_SCK") (class "Default")
      (node (ref "U2") (pin "12") (pinfunction "IO8_12") (pintype "bidirectional"))
      (node (ref "U4") (pin "P$3") (pinfunction "LR_SCK_3_P$3") (pintype "bidirectional"))
    )
    (net (code "19") (name "IO9_G_A2") (class "Default")
      (node (ref "J4") (pin "2") (pinfunction "2_2") (pintype "bidirectional"))
      (node (ref "P7") (pin "P$1") (pinfunction "P$1_P$1") (pintype "bidirectional"))
      (node (ref "U2") (pin "17") (pinfunction "IO9_17") (pintype "bidirectional"))
    )
    (net (code "20") (name "IO10_G_A2") (class "Default")
      (node (ref "J4") (pin "1") (pinfunction "1_1") (pintype "bidirectional"))
      (node (ref "P8") (pin "P$1") (pinfunction "P$1_P$1") (pintype "bidirectional"))
      (node (ref "U2") (pin "18") (pinfunction "IO10_18") (pintype "bidirectional"))
    )
    (net (code "21") (name "IO11_G_D1") (class "Default")
      (node (ref "J5") (pin "2") (pinfunction "2_2") (pintype "bidirectional"))
      (node (ref "P20") (pin "P$1") (pinfunction "P$1_P$1") (pintype "bidirectional"))
      (node (ref "U2") (pin "19") (pinfunction "IO11_19") (pintype "bidirectional"))
    )
    (net (code "22") (name "IO12_G_D1") (class "Default")
      (node (ref "J5") (pin "1") (pinfunction "1_1") (pintype "bidirectional"))
      (node (ref "P21") (pin "P$1") (pinfunction "P$1_P$1") (pintype "bidirectional"))
      (node (ref "U2") (pin "20") (pinfunction "IO12_20") (pintype "bidirectional"))
    )
    (net (code "23") (name "IO13_G_D2") (class "Default")
      (node (ref "J6") (pin "2") (pinfunction "2_2") (pintype "bidirectional"))
      (node (ref "P22") (pin "P$1") (pinfunction "P$1_P$1") (pintype "bidirectional"))
      (node (ref "U2") (pin "21") (pinfunction "IO13_21") (pintype "bidirectional"))
    )
    (net (code "24") (name "IO14_G_D2") (class "Default")
      (node (ref "J6") (pin "1") (pinfunction "1_1") (pintype "bidirectional"))
      (node (ref "P23") (pin "P$1") (pinfunction "P$1_P$1") (pintype "bidirectional"))
      (node (ref "U2") (pin "22") (pinfunction "IO14_22") (pintype "bidirectional"))
    )
    (net (code "25") (name "IO15_G_A1") (class "Default")
      (node (ref "J3") (pin "2") (pinfunction "2_2") (pintype "bidirectional"))
      (node (ref "P9") (pin "P$1") (pinfunction "P$1_P$1") (pintype "bidirectional"))
      (node (ref "U2") (pin "8") (pinfunction "IO15_8") (pintype "bidirectional"))
    )
    (net (code "26") (name "IO16_G_A1") (class "Default")
      (node (ref "J3") (pin "1") (pinfunction "1_1") (pintype "bidirectional"))
      (node (ref "P10") (pin "P$1") (pinfunction "P$1_P$1") (pintype "bidirectional"))
      (node (ref "U2") (pin "9") (pinfunction "IO16_9") (pintype "bidirectional"))
    )
    (net (code "27") (name "IO17_SPI_MISO") (class "Default")
      (node (ref "U2") (pin "10") (pinfunction "IO17_10") (pintype "bidirectional"))
      (node (ref "U4") (pin "P$5") (pinfunction "LR_MISO_5_P$5") (pintype "bidirectional"))
    )
    (net (code "28") (name "IO18_SPI_MOSI") (class "Default")
      (node (ref "U2") (pin "11") (pinfunction "IO18_11") (pintype "bidirectional"))
      (node (ref "U4") (pin "P$4") (pinfunction "LR_MOSI_4_P$4") (pintype "bidirectional"))
    )
    (net (code "29") (name "IO19_UART_RX") (class "Default")
      (node (ref "J7") (pin "1") (pinfunction "1_1") (pintype "bidirectional"))
      (node (ref "P17") (pin "P$1") (pinfunction "P$1_P$1") (pintype "bidirectional"))
      (node (ref "U2") (pin "13") (pinfunction "IO19_13") (pintype "bidirectional"))
    )
    (net (code "30") (name "IO20_UART_TX") (class "Default")
      (node (ref "J7") (pin "2") (pinfunction "2_2") (pintype "bidirectional"))
      (node (ref "P16") (pin "P$1") (pinfunction "P$1_P$1") (pintype "bidirectional"))
      (node (ref "U2") (pin "14") (pinfunction "IO20_14") (pintype "bidirectional"))
    )
    (net (code "31") (name "IO21_LED") (class "Default")
      (node (ref "LED2") (pin "-") (pinfunction "-_-") (pintype "passive"))
      (node (ref "U2") (pin "23") (pinfunction "IO21_23") (pintype "bidirectional"))
    )
    (net (code "32") (name "IO38_SDA_1") (class "Default")
      (node (ref "J10") (pin "2") (pinfunction "2_2") (pintype "bidirectional"))
      (node (ref "P25") (pin "P$1") (pinfunction "P$1_P$1") (pintype "bidirectional"))
      (node (ref "R17") (pin "1") (pinfunction "1_1") (pintype "passive"))
      (node (ref "U2") (pin "31") (pinfunction "IO38_31") (pintype "bidirectional"))
    )
    (net (code "33") (name "IO39_SCL_1") (class "Default")
      (node (ref "J10") (pin "1") (pinfunction "1_1") (pintype "bidirectional"))
      (node (ref "P26") (pin "P$1") (pinfunction "P$1_P$1") (pintype "bidirectional"))
      (node (ref "R18") (pin "1") (pinfunction "1_1") (pintype "passive"))
      (node (ref "U2") (pin "32") (pinfunction "IO39_32") (pintype "bidirectional"))
    )
    (net (code "34") (name "IO40_SDA_0") (class "Default")
      (node (ref "J8") (pin "2") (pinfunction "2_2") (pintype "bidirectional"))
      (node (ref "J9") (pin "2") (pinfunction "2_2") (pintype "bidirectional"))
      (node (ref "P13") (pin "P$1") (pinfunction "P$1_P$1") (pintype "bidirectional"))
      (node (ref "R16") (pin "1") (pinfunction "1_1") (pintype "passive"))
      (node (ref "U2") (pin "33") (pinfunction "IO40_33") (pintype "bidirectional"))
    )
    (net (code "35") (name "IO41_SCL_0") (class "Default")
      (node (ref "J8") (pin "1") (pinfunction "1_1") (pintype "bidirectional"))
      (node (ref "J9") (pin "1") (pinfunction "1_1") (pintype "bidirectional"))
      (node (ref "P24") (pin "P$1") (pinfunction "P$1_P$1") (pintype "bidirectional"))
      (node (ref "R21") (pin "1") (pinfunction "1_1") (pintype "passive"))
      (node (ref "U2") (pin "34") (pinfunction "IO41_34") (pintype "bidirectional"))
    )
    (net (code "36") (name "Net-(C11-Pad1)") (class "Default")
      (node (ref "C11") (pin "1") (pinfunction "1_1") (pintype "passive"))
      (node (ref "D15") (pin "2") (pinfunction "2_2") (pintype "bidirectional"))
      (node (ref "LR_ANT") (pin "P$1") (pinfunction "P$1_P$1") (pintype "bidirectional"))
      (node (ref "R14") (pin "2") (pinfunction "2_2") (pintype "passive"))
    )
    (net (code "37") (name "Net-(J1-PadA5)") (class "Default")
      (node (ref "J1") (pin "A5") (pinfunction "A5_A5") (pintype "bidirectional"))
      (node (ref "R2") (pin "2") (pinfunction "2_2") (pintype "passive"))
    )
    (net (code "38") (name "Net-(J1-PadB5)") (class "Default")
      (node (ref "J1") (pin "B5") (pinfunction "B5_B5") (pintype "bidirectional"))
      (node (ref "R1") (pin "1") (pinfunction "1_1") (pintype "passive"))
    )
    (net (code "39") (name "Net-(LED1-Pad+)") (class "Default")
      (node (ref "LED1") (pin "+") (pinfunction "+_+") (pintype "passive"))
      (node (ref "R13") (pin "1") (pinfunction "1_1") (pintype "passive"))
    )
    (net (code "40") (name "Net-(LED2-Pad+)") (class "Default")
      (node (ref "LED2") (pin "+") (pinfunction "+_+") (pintype "passive"))
      (node (ref "R12") (pin "1") (pinfunction "1_1") (pintype "passive"))
    )
    (net (code "41") (name "Net-(Q3-G)") (class "Default")
      (node (ref "Q3") (pin "1") (pinfunction "G_1") (pintype "bidirectional"))
      (node (ref "R11") (pin "2") (pinfunction "2_2") (pintype "passive"))
      (node (ref "R4") (pin "1") (pinfunction "1_1") (pintype "passive"))
    )
    (net (code "42") (name "Net-(U1-RXD)") (class "Default")
      (node (ref "R8") (pin "2") (pinfunction "2_2") (pintype "passive"))
      (node (ref "U1") (pin "9") (pinfunction "RXD_9") (pintype "bidirectional"))
    )
    (net (code "43") (name "Net-(U1-TXD)") (class "Default")
      (node (ref "R10") (pin "2") (pinfunction "2_2") (pintype "passive"))
      (node (ref "U1") (pin "8") (pinfunction "TXD_8") (pintype "bidirectional"))
    )
    (net (code "44") (name "Net-(U1-UD+)") (class "Default")
      (node (ref "R6") (pin "1") (pinfunction "1_1") (pintype "passive"))
      (node (ref "U1") (pin "1") (pinfunction "UD+_1") (pintype "bidirectional"))
    )
    (net (code "45") (name "Net-(U1-UD-)") (class "Default")
      (node (ref "R7") (pin "1") (pinfunction "1_1") (pintype "passive"))
      (node (ref "U1") (pin "2") (pinfunction "UD-_2") (pintype "bidirectional"))
    )
    (net (code "46") (name "Net-(U3-FB)") (class "Default")
      (node (ref "R19") (pin "1") (pinfunction "1_1") (pintype "passive"))
      (node (ref "R20") (pin "2") (pinfunction "2_2") (pintype "passive"))
      (node (ref "U3") (pin "5") (pinfunction "FB_5") (pintype "bidirectional"))
    )
    (net (code "47") (name "Net-(U3-SW)") (class "Default")
      (node (ref "L4") (pin "1") (pinfunction "1_1") (pintype "passive"))
      (node (ref "U3") (pin "3") (pinfunction "SW_3") (pintype "bidirectional"))
    )
    (net (code "48") (name "Net-(U4-VDD_3V3_1)") (class "Default")
      (node (ref "C12") (pin "1") (pinfunction "1_1") (pintype "passive"))
      (node (ref "C13") (pin "1") (pinfunction "1_1") (pintype "passive"))
      (node (ref "C14") (pin "1") (pinfunction "1_1") (pintype "passive"))
      (node (ref "FB2") (pin "2") (pinfunction "2_2") (pintype "passive"))
      (node (ref "U4") (pin "P$1") (pinfunction "VDD_3V3_1_P$1") (pintype "bidirectional"))
    )
    (net (code "49") (name "Net-(U6-PROG)") (class "Default")
      (node (ref "R3") (pin "2") (pinfunction "2_2") (pintype "passive"))
      (node (ref "U6") (pin "5") (pinfunction "PROG_5") (pintype "bidirectional"))
    )
    (net (code "50") (name "Net-(U8-B1)") (class "Default")
      (node (ref "R5") (pin "1") (pinfunction "1_1") (pintype "passive"))
      (node (ref "U8") (pin "2") (pinfunction "B1_2") (pintype "input"))
    )
    (net (code "51") (name "Net-(U8-B2)") (class "Default")
      (node (ref "R9") (pin "1") (pinfunction "1_1") (pintype "passive"))
      (node (ref "U8") (pin "5") (pinfunction "B2_5") (pintype "input"))
    )
    (net (code "52") (name "RTS") (class "Default")
      (node (ref "R9") (pin "2") (pinfunction "2_2") (pintype "passive"))
      (node (ref "U1") (pin "6") (pinfunction "RTS#_6") (pintype "bidirectional"))
      (node (ref "U8") (pin "1") (pinfunction "E1_1") (pintype "bidirectional"))
    )
    (net (code "53") (name "USB_D+") (class "Default")
      (node (ref "J1") (pin "A6") (pinfunction "A6_A6") (pintype "bidirectional"))
      (node (ref "J1") (pin "B6") (pinfunction "B6_B6") (pintype "bidirectional"))
      (node (ref "P2") (pin "P$1") (pinfunction "P$1_P$1") (pintype "bidirectional"))
      (node (ref "R6") (pin "2") (pinfunction "2_2") (pintype "passive"))
    )
    (net (code "54") (name "USB_D-") (class "Default")
      (node (ref "J1") (pin "A7") (pinfunction "A7_A7") (pintype "bidirectional"))
      (node (ref "J1") (pin "B7") (pinfunction "B7_B7") (pintype "bidirectional"))
      (node (ref "P3") (pin "P$1") (pinfunction "P$1_P$1") (pintype "bidirectional"))
      (node (ref "R7") (pin "2") (pinfunction "2_2") (pintype "passive"))
    )
    (net (code "55") (name "VIN") (class "Default")
      (node (ref "C6") (pin "1") (pinfunction "1_1") (pintype "passive"))
      (node (ref "C7") (pin "2") (pinfunction "2_2") (pintype "passive"))
      (node (ref "D1") (pin "-") (pinfunction "-_-") (pintype "passive"))
      (node (ref "D10") (pin "-") (pinfunction "-_-") (pintype "passive"))
      (node (ref "Q3") (pin "2") (pinfunction "S_2") (pintype "bidirectional"))
      (node (ref "U3") (pin "1") (pinfunction "EN_1") (pintype "bidirectional"))
      (node (ref "U3") (pin "4") (pinfunction "VIN_4") (pintype "bidirectional"))
    )
    (net (code "56") (name "unconnected-(J1-PadA8)") (class "Default")
      (node (ref "J1") (pin "A8") (pinfunction "A8_A8") (pintype "bidirectional"))
    )
    (net (code "57") (name "unconnected-(J1-PadB8)") (class "Default")
      (node (ref "J1") (pin "B8") (pinfunction "B8_B8") (pintype "bidirectional"))
    )
    (net (code "58") (name "unconnected-(U1-CTS#-Pad5)") (class "Default")
      (node (ref "U1") (pin "5") (pinfunction "CTS#_5") (pintype "bidirectional"))
    )
    (net (code "59") (name "unconnected-(U2-IO1-Pad39)") (class "Default")
      (node (ref "U2") (pin "39") (pinfunction "IO1_39") (pintype "bidirectional"))
    )
    (net (code "60") (name "unconnected-(U2-IO2-Pad38)") (class "Default")
      (node (ref "U2") (pin "38") (pinfunction "IO2_38") (pintype "bidirectional"))
    )
    (net (code "61") (name "unconnected-(U2-IO35-Pad28)") (class "Default")
      (node (ref "U2") (pin "28") (pinfunction "IO35_28") (pintype "bidirectional"))
    )
    (net (code "62") (name "unconnected-(U2-IO36-Pad29)") (class "Default")
      (node (ref "U2") (pin "29") (pinfunction "IO36_29") (pintype "bidirectional"))
    )
    (net (code "63") (name "unconnected-(U2-IO37-Pad30)") (class "Default")
      (node (ref "U2") (pin "30") (pinfunction "IO37_30") (pintype "bidirectional"))
    )
    (net (code "64") (name "unconnected-(U2-IO42-Pad35)") (class "Default")
      (node (ref "U2") (pin "35") (pinfunction "IO42_35") (pintype "bidirectional"))
    )
    (net (code "65") (name "unconnected-(U2-IO45-Pad26)") (class "Default")
      (node (ref "U2") (pin "26") (pinfunction "IO45_26") (pintype "bidirectional"))
    )
    (net (code "66") (name "unconnected-(U2-IO46-Pad16)") (class "Default")
      (node (ref "U2") (pin "16") (pinfunction "IO46_16") (pintype "bidirectional"))
    )
    (net (code "67") (name "unconnected-(U2-IO47-Pad24)") (class "Default")
      (node (ref "U2") (pin "24") (pinfunction "IO47_24") (pintype "bidirectional"))
    )
    (net (code "68") (name "unconnected-(U2-IO48-Pad25)") (class "Default")
      (node (ref "U2") (pin "25") (pinfunction "IO48_25") (pintype "bidirectional"))
    )
    (net (code "69") (name "unconnected-(U6-GHRG-Pad1)") (class "Default")
      (node (ref "U6") (pin "1") (pinfunction "GHRG_1") (pintype "bidirectional"))
    )
  )
)
